# Power.net
KiCad netlist of a schematic drawn in Altium Designer
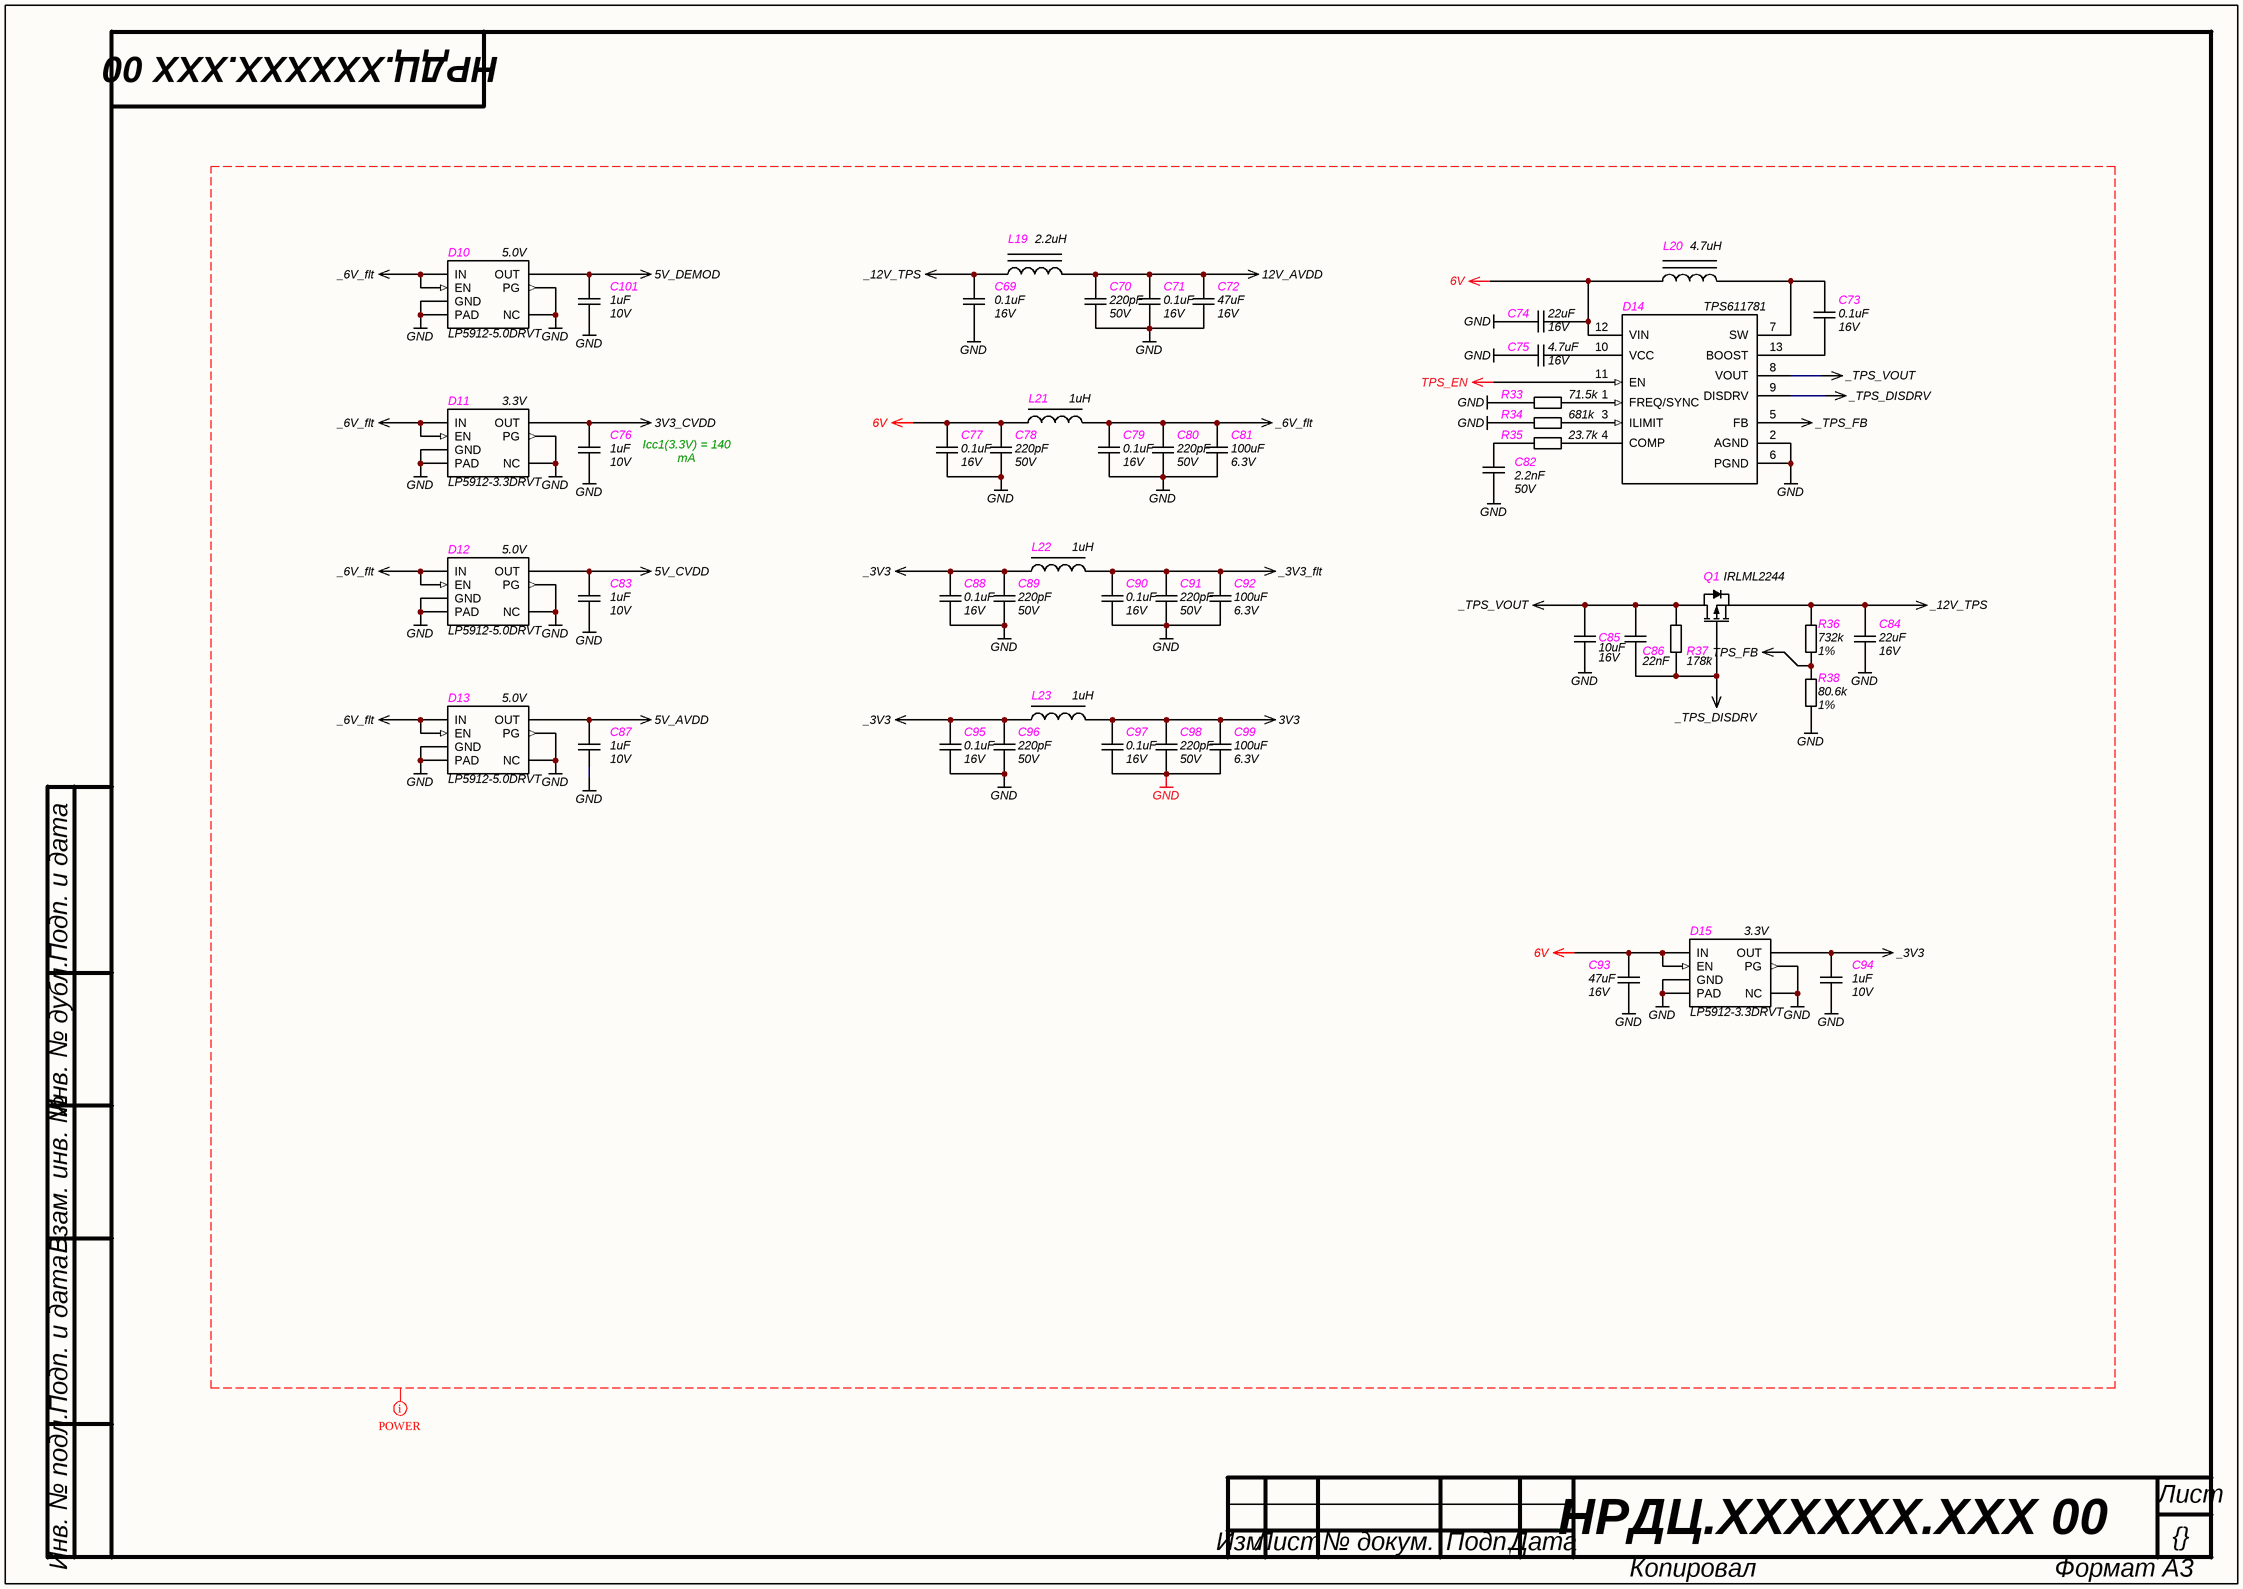
[diagram p0: Power.SchDoc]

(export (version "E")
  (design (tool "Eeschema 10.0.6"))
  (components
    (comp (ref "C69")
      (value "0.1uF")
      (footprint "C0402")
      (description "SMD Capacitor")
      (fields
        (field (name "MANUFACTURER") "Murata")
        (field (name "TOLERANCE") "10%")
        (field (name "VOLTAGE") "16V")
      )
      (libsource (lib "Kintex_SDR") (part "CAP"))
    )
    (comp (ref "C70")
      (value "220pF")
      (footprint "C0603")
      (description "SMD Capacitor")
      (fields
        (field (name "MANUFACTURER") "KEMET")
        (field (name "TOLERANCE") "10%")
        (field (name "VOLTAGE") "50V")
      )
      (libsource (lib "Kintex_SDR") (part "CAP"))
    )
    (comp (ref "C71")
      (value "0.1uF")
      (footprint "C0402")
      (description "SMD Capacitor")
      (fields
        (field (name "MANUFACTURER") "Murata")
        (field (name "TOLERANCE") "10%")
        (field (name "VOLTAGE") "16V")
      )
      (libsource (lib "Kintex_SDR") (part "CAP"))
    )
    (comp (ref "C72")
      (value "47uF")
      (footprint "C1210")
      (description "SMD Capacitor")
      (fields
        (field (name "MANUFACTURER") "Murata")
        (field (name "TOLERANCE") "10%")
        (field (name "VOLTAGE") "16V")
      )
      (libsource (lib "Kintex_SDR") (part "CAP uF"))
    )
    (comp (ref "C73")
      (value "0.1uF")
      (footprint "C0402")
      (description "SMD Capacitor")
      (fields
        (field (name "MANUFACTURER") "Murata")
        (field (name "TOLERANCE") "10%")
        (field (name "VOLTAGE") "16V")
      )
      (libsource (lib "Kintex_SDR") (part "CAP"))
    )
    (comp (ref "C74")
      (value "22uF")
      (footprint "C0805")
      (description "SMD Capacitor")
      (fields
        (field (name "MANUFACTURER") "Murata")
        (field (name "TOLERANCE") "±20%")
        (field (name "VOLTAGE") "16V")
      )
      (libsource (lib "Kintex_SDR") (part "CAP uF"))
    )
    (comp (ref "C75")
      (value "4.7uF")
      (footprint "C0603")
      (description "SMD Capacitor")
      (fields
        (field (name "MANUFACTURER") "Murata")
        (field (name "TOLERANCE") "10%")
        (field (name "VOLTAGE") "16V")
      )
      (libsource (lib "Kintex_SDR") (part "CAP"))
    )
    (comp (ref "C76")
      (value "1uF")
      (footprint "C0805")
      (description "SMD Capacitor")
      (fields
        (field (name "MANUFACTURER") "Murata")
        (field (name "TOLERANCE") "10%")
        (field (name "VOLTAGE") "10V")
      )
      (libsource (lib "Kintex_SDR") (part "CAP"))
    )
    (comp (ref "C77")
      (value "0.1uF")
      (footprint "C0402")
      (description "SMD Capacitor")
      (fields
        (field (name "MANUFACTURER") "Murata")
        (field (name "TOLERANCE") "10%")
        (field (name "VOLTAGE") "16V")
      )
      (libsource (lib "Kintex_SDR") (part "CAP"))
    )
    (comp (ref "C78")
      (value "220pF")
      (footprint "C0603")
      (description "SMD Capacitor")
      (fields
        (field (name "MANUFACTURER") "KEMET")
        (field (name "TOLERANCE") "10%")
        (field (name "VOLTAGE") "50V")
      )
      (libsource (lib "Kintex_SDR") (part "CAP"))
    )
    (comp (ref "C79")
      (value "0.1uF")
      (footprint "C0402")
      (description "SMD Capacitor")
      (fields
        (field (name "MANUFACTURER") "Murata")
        (field (name "TOLERANCE") "10%")
        (field (name "VOLTAGE") "16V")
      )
      (libsource (lib "Kintex_SDR") (part "CAP"))
    )
    (comp (ref "C80")
      (value "220pF")
      (footprint "C0603")
      (description "SMD Capacitor")
      (fields
        (field (name "MANUFACTURER") "KEMET")
        (field (name "TOLERANCE") "10%")
        (field (name "VOLTAGE") "50V")
      )
      (libsource (lib "Kintex_SDR") (part "CAP"))
    )
    (comp (ref "C81")
      (value "100uF")
      (footprint "C1210")
      (description "SMD Capacitor")
      (fields
        (field (name "MANUFACTURER") "Murata")
        (field (name "TOLERANCE") "20%")
        (field (name "VOLTAGE") "6.3V")
      )
      (libsource (lib "Kintex_SDR") (part "CAP uF"))
    )
    (comp (ref "C82")
      (value "2.2nF")
      (footprint "C0603")
      (description "SMD Capacitor")
      (fields
        (field (name "MANUFACTURER") "Murata")
        (field (name "TOLERANCE") "±5%")
        (field (name "VOLTAGE") "50V")
      )
      (libsource (lib "Kintex_SDR") (part "CAP"))
    )
    (comp (ref "C83")
      (value "1uF")
      (footprint "C0805")
      (description "SMD Capacitor")
      (fields
        (field (name "MANUFACTURER") "Murata")
        (field (name "TOLERANCE") "10%")
        (field (name "VOLTAGE") "10V")
      )
      (libsource (lib "Kintex_SDR") (part "CAP"))
    )
    (comp (ref "C84")
      (value "22uF")
      (footprint "C0805")
      (description "SMD Capacitor")
      (fields
        (field (name "MANUFACTURER") "Murata")
        (field (name "TOLERANCE") "±20%")
        (field (name "VOLTAGE") "16V")
      )
      (libsource (lib "Kintex_SDR") (part "CAP uF"))
    )
    (comp (ref "C85")
      (value "10uF")
      (footprint "C0805")
      (description "SMD Capacitor")
      (fields
        (field (name "MANUFACTURER") "Murata")
        (field (name "TOLERANCE") "±10%")
        (field (name "VOLTAGE") "16V")
      )
      (libsource (lib "Kintex_SDR") (part "CAP uF"))
    )
    (comp (ref "C86")
      (value "22nF")
      (footprint "C0402")
      (description "SMD Capacitor")
      (fields (field (name "MANUFACTURER") "Murata") (field (name "TOLERANCE") "10%"))
      (libsource (lib "Kintex_SDR") (part "CAP"))
    )
    (comp (ref "C87")
      (value "1uF")
      (footprint "C0805")
      (description "SMD Capacitor")
      (fields
        (field (name "MANUFACTURER") "Murata")
        (field (name "TOLERANCE") "10%")
        (field (name "VOLTAGE") "10V")
      )
      (libsource (lib "Kintex_SDR") (part "CAP"))
    )
    (comp (ref "C88")
      (value "0.1uF")
      (footprint "C0402")
      (description "SMD Capacitor")
      (fields
        (field (name "MANUFACTURER") "Murata")
        (field (name "TOLERANCE") "10%")
        (field (name "VOLTAGE") "16V")
      )
      (libsource (lib "Kintex_SDR") (part "CAP"))
    )
    (comp (ref "C89")
      (value "220pF")
      (footprint "C0603")
      (description "SMD Capacitor")
      (fields
        (field (name "MANUFACTURER") "KEMET")
        (field (name "TOLERANCE") "10%")
        (field (name "VOLTAGE") "50V")
      )
      (libsource (lib "Kintex_SDR") (part "CAP"))
    )
    (comp (ref "C90")
      (value "0.1uF")
      (footprint "C0402")
      (description "SMD Capacitor")
      (fields
        (field (name "MANUFACTURER") "Murata")
        (field (name "TOLERANCE") "10%")
        (field (name "VOLTAGE") "16V")
      )
      (libsource (lib "Kintex_SDR") (part "CAP"))
    )
    (comp (ref "C91")
      (value "220pF")
      (footprint "C0603")
      (description "SMD Capacitor")
      (fields
        (field (name "MANUFACTURER") "KEMET")
        (field (name "TOLERANCE") "10%")
        (field (name "VOLTAGE") "50V")
      )
      (libsource (lib "Kintex_SDR") (part "CAP"))
    )
    (comp (ref "C92")
      (value "100uF")
      (footprint "C1210")
      (description "SMD Capacitor")
      (fields
        (field (name "MANUFACTURER") "Murata")
        (field (name "TOLERANCE") "20%")
        (field (name "VOLTAGE") "6.3V")
      )
      (libsource (lib "Kintex_SDR") (part "CAP uF"))
    )
    (comp (ref "C93")
      (value "47uF")
      (footprint "C1210")
      (description "SMD Capacitor")
      (fields
        (field (name "MANUFACTURER") "Murata")
        (field (name "TOLERANCE") "10%")
        (field (name "VOLTAGE") "16V")
      )
      (libsource (lib "Kintex_SDR") (part "CAP uF"))
    )
    (comp (ref "C94")
      (value "1uF")
      (footprint "C0805")
      (description "SMD Capacitor")
      (fields
        (field (name "MANUFACTURER") "Murata")
        (field (name "TOLERANCE") "10%")
        (field (name "VOLTAGE") "10V")
      )
      (libsource (lib "Kintex_SDR") (part "CAP"))
    )
    (comp (ref "C95")
      (value "0.1uF")
      (footprint "C0402")
      (description "SMD Capacitor")
      (fields
        (field (name "MANUFACTURER") "Murata")
        (field (name "TOLERANCE") "10%")
        (field (name "VOLTAGE") "16V")
      )
      (libsource (lib "Kintex_SDR") (part "CAP"))
    )
    (comp (ref "C96")
      (value "220pF")
      (footprint "C0603")
      (description "SMD Capacitor")
      (fields
        (field (name "MANUFACTURER") "KEMET")
        (field (name "TOLERANCE") "10%")
        (field (name "VOLTAGE") "50V")
      )
      (libsource (lib "Kintex_SDR") (part "CAP"))
    )
    (comp (ref "C97")
      (value "0.1uF")
      (footprint "C0402")
      (description "SMD Capacitor")
      (fields
        (field (name "MANUFACTURER") "Murata")
        (field (name "TOLERANCE") "10%")
        (field (name "VOLTAGE") "16V")
      )
      (libsource (lib "Kintex_SDR") (part "CAP"))
    )
    (comp (ref "C98")
      (value "220pF")
      (footprint "C0603")
      (description "SMD Capacitor")
      (fields
        (field (name "MANUFACTURER") "KEMET")
        (field (name "TOLERANCE") "10%")
        (field (name "VOLTAGE") "50V")
      )
      (libsource (lib "Kintex_SDR") (part "CAP"))
    )
    (comp (ref "C99")
      (value "100uF")
      (footprint "C1210")
      (description "SMD Capacitor")
      (fields
        (field (name "MANUFACTURER") "Murata")
        (field (name "TOLERANCE") "20%")
        (field (name "VOLTAGE") "6.3V")
      )
      (libsource (lib "Kintex_SDR") (part "CAP uF"))
    )
    (comp (ref "C101")
      (value "1uF")
      (footprint "C0805")
      (description "SMD Capacitor")
      (fields
        (field (name "MANUFACTURER") "Murata")
        (field (name "TOLERANCE") "10%")
        (field (name "VOLTAGE") "10V")
      )
      (libsource (lib "Kintex_SDR") (part "CAP"))
    )
    (comp (ref "D10")
      (value "LP5912")
      (footprint "DBLib:WSON-6")
      (description "LP5912 500-mA Low-Noise, Low-IQ LDO")
      (fields
        (field (name "MANUFACTURER") "Texas Instruments")
        (field (name "NAME") "LP5912-5.0DRVT")
        (field (name "VOLTAGE") "5.0V")
      )
      (libsource (lib "DBLib") (part "LP5912"))
    )
    (comp (ref "D11")
      (value "LP5912")
      (footprint "DBLib:WSON-6")
      (description "LP5912 500-mA Low-Noise, Low-IQ LDO")
      (fields
        (field (name "MANUFACTURER") "Texas Instruments")
        (field (name "NAME") "LP5912-3.3DRVT")
        (field (name "VOLTAGE") "3.3V")
      )
      (libsource (lib "DBLib") (part "LP5912"))
    )
    (comp (ref "D12")
      (value "LP5912")
      (footprint "DBLib:WSON-6")
      (description "LP5912 500-mA Low-Noise, Low-IQ LDO")
      (fields
        (field (name "MANUFACTURER") "Texas Instruments")
        (field (name "NAME") "LP5912-5.0DRVT")
        (field (name "VOLTAGE") "5.0V")
      )
      (libsource (lib "DBLib") (part "LP5912"))
    )
    (comp (ref "D13")
      (value "LP5912")
      (footprint "DBLib:WSON-6")
      (description "LP5912 500-mA Low-Noise, Low-IQ LDO")
      (fields
        (field (name "MANUFACTURER") "Texas Instruments")
        (field (name "NAME") "LP5912-5.0DRVT")
        (field (name "VOLTAGE") "5.0V")
      )
      (libsource (lib "DBLib") (part "LP5912"))
    )
    (comp (ref "D14")
      (value "TPS611781")
      (footprint "DBLib:TPS611781x")
      (description "10-A Fully-Integrated Synchronous Boost with Load Disconnect Control")
      (fields (field (name "MANUFACTURER") "Texas Instruments") (field (name "VOLTAGE") "4.5 V to 20 V"))
      (libsource (lib "DBLib") (part "TPS611781"))
    )
    (comp (ref "D15")
      (value "LP5912")
      (footprint "DBLib:WSON-6")
      (description "LP5912 500-mA Low-Noise, Low-IQ LDO")
      (fields
        (field (name "MANUFACTURER") "Texas Instruments")
        (field (name "NAME") "LP5912-3.3DRVT")
        (field (name "VOLTAGE") "3.3V")
      )
      (libsource (lib "DBLib") (part "LP5912"))
    )
    (comp (ref "L19")
      (value "2.2uH")
      (footprint "XAL4020")
      (description "Magnetic-Core Inductor")
      (fields (field (name "MANUFACTURER") "Coilcraft") (field (name "TOLERANCE") "±30%"))
      (libsource (lib "Kintex_SDR") (part "Inductor PWR"))
    )
    (comp (ref "L20")
      (value "4.7uH")
      (footprint "XAL4030")
      (description "Magnetic-Core Inductor")
      (fields (field (name "MANUFACTURER") "Coilcraft") (field (name "TOLERANCE") "±30%"))
      (libsource (lib "Kintex_SDR") (part "Inductor PWR"))
    )
    (comp (ref "L21")
      (value "1uH")
      (footprint "L1210_Murata LQH")
      (description "Inductor Power Lines")
      (fields (field (name "MANUFACTURER") "Murata") (field (name "TOLERANCE") "5%"))
      (libsource (lib "Kintex_SDR") (part "Inductor LF"))
    )
    (comp (ref "L22")
      (value "1uH")
      (footprint "L1210_Murata LQH")
      (description "Inductor Power Lines")
      (fields (field (name "MANUFACTURER") "Murata") (field (name "TOLERANCE") "5%"))
      (libsource (lib "Kintex_SDR") (part "Inductor LF"))
    )
    (comp (ref "L23")
      (value "1uH")
      (footprint "L1210_Murata LQH")
      (description "Inductor Power Lines")
      (fields (field (name "MANUFACTURER") "Murata") (field (name "TOLERANCE") "5%"))
      (libsource (lib "Kintex_SDR") (part "Inductor LF"))
    )
    (comp (ref "Q1")
      (value "IRLML2244")
      (footprint "DBLib:SOT-23")
      (description "P-Channel MOSFET")
      (fields (field (name "VOLTAGE") "-20V"))
      (libsource (lib "DBLib") (part "IRLML2244"))
    )
    (comp (ref "R33")
      (value "71.5k")
      (footprint "R0402")
      (description "SMD Resistor")
      (fields (field (name "POWER") "0.063 Wt") (field (name "TOLERANCE") "1%"))
      (libsource (lib "Kintex_SDR") (part "RES"))
    )
    (comp (ref "R34")
      (value "681k")
      (footprint "R0402")
      (description "SMD Resistor")
      (fields (field (name "POWER") "0.063 Wt") (field (name "TOLERANCE") "1%"))
      (libsource (lib "Kintex_SDR") (part "RES"))
    )
    (comp (ref "R35")
      (value "23.7k")
      (footprint "R0603")
      (description "SMD Resistor")
      (fields (field (name "POWER") "0.1 Wt") (field (name "TOLERANCE") "1%"))
      (libsource (lib "Kintex_SDR") (part "RES"))
    )
    (comp (ref "R36")
      (value "732k")
      (footprint "R0402")
      (description "SMD Resistor")
      (fields
        (field (name "POWER") "0.063 Wt")
        (field (name "TOLERANCE") "1%")
        (field (name "MANUFACTURER") "Panasonic Electronic Components")
      )
      (libsource (lib "") (part "RES_1"))
    )
    (comp (ref "R37")
      (value "178k")
      (footprint "R0402")
      (description "SMD Resistor")
      (fields (field (name "POWER") "0.063 Wt") (field (name "TOLERANCE") "1%"))
      (libsource (lib "") (part "RES_1"))
    )
    (comp (ref "R38")
      (value "80.6k")
      (footprint "R0402")
      (description "SMD Resistor")
      (fields
        (field (name "POWER") "0.063 Wt")
        (field (name "TOLERANCE") "1%")
        (field (name "MANUFACTURER") "Panasonic Electronic Components")
      )
      (libsource (lib "") (part "RES_1"))
    )
  )
  (nets
    (net (code "1") (name "3V3") (class "Default")
      (node (ref "C97") (pin "2") (pinfunction "2_2") (pintype "passive"))
      (node (ref "C98") (pin "2") (pinfunction "2_2") (pintype "passive"))
      (node (ref "C99") (pin "2") (pinfunction "2_2") (pintype "passive"))
      (node (ref "L23") (pin "2") (pinfunction "2_2") (pintype "passive"))
    )
    (net (code "2") (name "3V3_CVDD") (class "Default")
      (node (ref "C76") (pin "1") (pinfunction "1_1") (pintype "passive"))
      (node (ref "D11") (pin "1") (pinfunction "OUT_1") (pintype "passive"))
    )
    (net (code "3") (name "5V_AVDD") (class "Default")
      (node (ref "C87") (pin "1") (pinfunction "1_1") (pintype "passive"))
      (node (ref "D13") (pin "1") (pinfunction "OUT_1") (pintype "passive"))
    )
    (net (code "4") (name "5V_CVDD") (class "Default")
      (node (ref "C83") (pin "1") (pinfunction "1_1") (pintype "passive"))
      (node (ref "D12") (pin "1") (pinfunction "OUT_1") (pintype "passive"))
    )
    (net (code "5") (name "5V_DEMOD") (class "Default")
      (node (ref "C101") (pin "1") (pinfunction "1_1") (pintype "passive"))
      (node (ref "D10") (pin "1") (pinfunction "OUT_1") (pintype "passive"))
    )
    (net (code "6") (name "6V") (class "Default")
      (node (ref "C74") (pin "1") (pinfunction "1_1") (pintype "passive"))
      (node (ref "C77") (pin "2") (pinfunction "2_2") (pintype "passive"))
      (node (ref "C78") (pin "2") (pinfunction "2_2") (pintype "passive"))
      (node (ref "C93") (pin "2") (pinfunction "2_2") (pintype "passive"))
      (node (ref "D14") (pin "12") (pinfunction "VIN_12") (pintype "passive"))
      (node (ref "D15") (pin "4") (pinfunction "EN_4") (pintype "input"))
      (node (ref "D15") (pin "6") (pinfunction "IN_6") (pintype "passive"))
      (node (ref "L20") (pin "1") (pinfunction "1_1") (pintype "passive"))
      (node (ref "L21") (pin "1") (pinfunction "1_1") (pintype "passive"))
    )
    (net (code "7") (name "12V_AVDD") (class "Default")
      (node (ref "C70") (pin "2") (pinfunction "2_2") (pintype "passive"))
      (node (ref "C71") (pin "2") (pinfunction "2_2") (pintype "passive"))
      (node (ref "C72") (pin "2") (pinfunction "2_2") (pintype "passive"))
      (node (ref "L19") (pin "2") (pinfunction "2_2") (pintype "passive"))
    )
    (net (code "8") (name "GND") (class "Default")
      (node (ref "C101") (pin "2") (pinfunction "2_2") (pintype "passive"))
      (node (ref "C69") (pin "1") (pinfunction "1_1") (pintype "passive"))
      (node (ref "C70") (pin "1") (pinfunction "1_1") (pintype "passive"))
      (node (ref "C71") (pin "1") (pinfunction "1_1") (pintype "passive"))
      (node (ref "C72") (pin "1") (pinfunction "1_1") (pintype "passive"))
      (node (ref "C74") (pin "2") (pinfunction "2_2") (pintype "passive"))
      (node (ref "C75") (pin "2") (pinfunction "2_2") (pintype "passive"))
      (node (ref "C76") (pin "2") (pinfunction "2_2") (pintype "passive"))
      (node (ref "C77") (pin "1") (pinfunction "1_1") (pintype "passive"))
      (node (ref "C78") (pin "1") (pinfunction "1_1") (pintype "passive"))
      (node (ref "C79") (pin "1") (pinfunction "1_1") (pintype "passive"))
      (node (ref "C80") (pin "1") (pinfunction "1_1") (pintype "passive"))
      (node (ref "C81") (pin "1") (pinfunction "1_1") (pintype "passive"))
      (node (ref "C82") (pin "1") (pinfunction "1_1") (pintype "passive"))
      (node (ref "C83") (pin "2") (pinfunction "2_2") (pintype "passive"))
      (node (ref "C84") (pin "1") (pinfunction "1_1") (pintype "passive"))
      (node (ref "C85") (pin "1") (pinfunction "1_1") (pintype "passive"))
      (node (ref "C87") (pin "2") (pinfunction "2_2") (pintype "passive"))
      (node (ref "C88") (pin "1") (pinfunction "1_1") (pintype "passive"))
      (node (ref "C89") (pin "1") (pinfunction "1_1") (pintype "passive"))
      (node (ref "C90") (pin "1") (pinfunction "1_1") (pintype "passive"))
      (node (ref "C91") (pin "1") (pinfunction "1_1") (pintype "passive"))
      (node (ref "C92") (pin "1") (pinfunction "1_1") (pintype "passive"))
      (node (ref "C93") (pin "1") (pinfunction "1_1") (pintype "passive"))
      (node (ref "C94") (pin "2") (pinfunction "2_2") (pintype "passive"))
      (node (ref "C95") (pin "1") (pinfunction "1_1") (pintype "passive"))
      (node (ref "C96") (pin "1") (pinfunction "1_1") (pintype "passive"))
      (node (ref "C97") (pin "1") (pinfunction "1_1") (pintype "passive"))
      (node (ref "C98") (pin "1") (pinfunction "1_1") (pintype "passive"))
      (node (ref "C99") (pin "1") (pinfunction "1_1") (pintype "passive"))
      (node (ref "D10") (pin "0") (pinfunction "PAD_0") (pintype "passive"))
      (node (ref "D10") (pin "2") (pinfunction "NC_2") (pintype "passive"))
      (node (ref "D10") (pin "3") (pinfunction "PG_3") (pintype "output"))
      (node (ref "D10") (pin "5") (pinfunction "GND_5") (pintype "passive"))
      (node (ref "D11") (pin "0") (pinfunction "PAD_0") (pintype "passive"))
      (node (ref "D11") (pin "2") (pinfunction "NC_2") (pintype "passive"))
      (node (ref "D11") (pin "3") (pinfunction "PG_3") (pintype "output"))
      (node (ref "D11") (pin "5") (pinfunction "GND_5") (pintype "passive"))
      (node (ref "D12") (pin "0") (pinfunction "PAD_0") (pintype "passive"))
      (node (ref "D12") (pin "2") (pinfunction "NC_2") (pintype "passive"))
      (node (ref "D12") (pin "3") (pinfunction "PG_3") (pintype "output"))
      (node (ref "D12") (pin "5") (pinfunction "GND_5") (pintype "passive"))
      (node (ref "D13") (pin "0") (pinfunction "PAD_0") (pintype "passive"))
      (node (ref "D13") (pin "2") (pinfunction "NC_2") (pintype "passive"))
      (node (ref "D13") (pin "3") (pinfunction "PG_3") (pintype "output"))
      (node (ref "D13") (pin "5") (pinfunction "GND_5") (pintype "passive"))
      (node (ref "D14") (pin "2") (pinfunction "AGND_2") (pintype "passive"))
      (node (ref "D14") (pin "6") (pinfunction "PGND_6") (pintype "passive"))
      (node (ref "D15") (pin "0") (pinfunction "PAD_0") (pintype "passive"))
      (node (ref "D15") (pin "2") (pinfunction "NC_2") (pintype "passive"))
      (node (ref "D15") (pin "3") (pinfunction "PG_3") (pintype "output"))
      (node (ref "D15") (pin "5") (pinfunction "GND_5") (pintype "passive"))
      (node (ref "R33") (pin "1") (pinfunction "1_1") (pintype "passive"))
      (node (ref "R34") (pin "1") (pinfunction "1_1") (pintype "passive"))
      (node (ref "R38") (pin "1") (pinfunction "1_1") (pintype "passive"))
    )
    (net (code "9") (name "Net-(C82-Pad2)") (class "Default")
      (node (ref "C82") (pin "2") (pinfunction "2_2") (pintype "passive"))
      (node (ref "R35") (pin "1") (pinfunction "1_1") (pintype "passive"))
    )
    (net (code "10") (name "Net-(D14-BOOST)") (class "Default")
      (node (ref "C73") (pin "1") (pinfunction "1_1") (pintype "passive"))
      (node (ref "D14") (pin "13") (pinfunction "BOOST_13") (pintype "passive"))
    )
    (net (code "11") (name "Net-(D14-COMP)") (class "Default")
      (node (ref "D14") (pin "4") (pinfunction "COMP_4") (pintype "passive"))
      (node (ref "R35") (pin "2") (pinfunction "2_2") (pintype "passive"))
    )
    (net (code "12") (name "Net-(D14-FREQ{slash}SYNC)") (class "Default")
      (node (ref "D14") (pin "1") (pinfunction "FREQ/SYNC_1") (pintype "input"))
      (node (ref "R33") (pin "2") (pinfunction "2_2") (pintype "passive"))
    )
    (net (code "13") (name "Net-(D14-ILIMIT)") (class "Default")
      (node (ref "D14") (pin "3") (pinfunction "ILIMIT_3") (pintype "input"))
      (node (ref "R34") (pin "2") (pinfunction "2_2") (pintype "passive"))
    )
    (net (code "14") (name "Net-(D14-SW)") (class "Default")
      (node (ref "C73") (pin "2") (pinfunction "2_2") (pintype "passive"))
      (node (ref "D14") (pin "7") (pinfunction "SW_7") (pintype "passive"))
      (node (ref "L20") (pin "2") (pinfunction "2_2") (pintype "passive"))
    )
    (net (code "15") (name "Net-(D14-VCC)") (class "Default")
      (node (ref "C75") (pin "1") (pinfunction "1_1") (pintype "passive"))
      (node (ref "D14") (pin "10") (pinfunction "VCC_10") (pintype "passive"))
    )
    (net (code "16") (name "TPS_EN") (class "Default")
      (node (ref "D14") (pin "11") (pinfunction "EN_11") (pintype "input"))
    )
    (net (code "17") (name "_3V3") (class "Default")
      (node (ref "C88") (pin "2") (pinfunction "2_2") (pintype "passive"))
      (node (ref "C89") (pin "2") (pinfunction "2_2") (pintype "passive"))
      (node (ref "C94") (pin "1") (pinfunction "1_1") (pintype "passive"))
      (node (ref "C95") (pin "2") (pinfunction "2_2") (pintype "passive"))
      (node (ref "C96") (pin "2") (pinfunction "2_2") (pintype "passive"))
      (node (ref "D15") (pin "1") (pinfunction "OUT_1") (pintype "passive"))
      (node (ref "L22") (pin "1") (pinfunction "1_1") (pintype "passive"))
      (node (ref "L23") (pin "1") (pinfunction "1_1") (pintype "passive"))
    )
    (net (code "18") (name "_3V3_flt") (class "Default")
      (node (ref "C90") (pin "2") (pinfunction "2_2") (pintype "passive"))
      (node (ref "C91") (pin "2") (pinfunction "2_2") (pintype "passive"))
      (node (ref "C92") (pin "2") (pinfunction "2_2") (pintype "passive"))
      (node (ref "L22") (pin "2") (pinfunction "2_2") (pintype "passive"))
    )
    (net (code "19") (name "_6V_flt") (class "Default")
      (node (ref "C79") (pin "2") (pinfunction "2_2") (pintype "passive"))
      (node (ref "C80") (pin "2") (pinfunction "2_2") (pintype "passive"))
      (node (ref "C81") (pin "2") (pinfunction "2_2") (pintype "passive"))
      (node (ref "D10") (pin "4") (pinfunction "EN_4") (pintype "input"))
      (node (ref "D10") (pin "6") (pinfunction "IN_6") (pintype "passive"))
      (node (ref "D11") (pin "4") (pinfunction "EN_4") (pintype "input"))
      (node (ref "D11") (pin "6") (pinfunction "IN_6") (pintype "passive"))
      (node (ref "D12") (pin "4") (pinfunction "EN_4") (pintype "input"))
      (node (ref "D12") (pin "6") (pinfunction "IN_6") (pintype "passive"))
      (node (ref "D13") (pin "4") (pinfunction "EN_4") (pintype "input"))
      (node (ref "D13") (pin "6") (pinfunction "IN_6") (pintype "passive"))
      (node (ref "L21") (pin "2") (pinfunction "2_2") (pintype "passive"))
    )
    (net (code "20") (name "_12V_TPS") (class "Default")
      (node (ref "C69") (pin "2") (pinfunction "2_2") (pintype "passive"))
      (node (ref "C84") (pin "2") (pinfunction "2_2") (pintype "passive"))
      (node (ref "L19") (pin "1") (pinfunction "1_1") (pintype "passive"))
      (node (ref "Q1") (pin "2") (pinfunction "S_2") (pintype "passive"))
      (node (ref "R36") (pin "2") (pinfunction "2_2") (pintype "passive"))
    )
    (net (code "21") (name "_TPS_DISDRV") (class "Default")
      (node (ref "C86") (pin "2") (pinfunction "2_2") (pintype "passive"))
      (node (ref "D14") (pin "9") (pinfunction "DISDRV_9") (pintype "passive"))
      (node (ref "Q1") (pin "1") (pinfunction "G_1") (pintype "passive"))
      (node (ref "R37") (pin "1") (pinfunction "1_1") (pintype "passive"))
    )
    (net (code "22") (name "_TPS_FB") (class "Default")
      (node (ref "D14") (pin "5") (pinfunction "FB_5") (pintype "passive"))
      (node (ref "R36") (pin "1") (pinfunction "1_1") (pintype "passive"))
      (node (ref "R38") (pin "2") (pinfunction "2_2") (pintype "passive"))
    )
    (net (code "23") (name "_TPS_VOUT") (class "Default")
      (node (ref "C85") (pin "2") (pinfunction "2_2") (pintype "passive"))
      (node (ref "C86") (pin "1") (pinfunction "1_1") (pintype "passive"))
      (node (ref "D14") (pin "8") (pinfunction "VOUT_8") (pintype "passive"))
      (node (ref "Q1") (pin "3") (pinfunction "D_3") (pintype "passive"))
      (node (ref "R37") (pin "2") (pinfunction "2_2") (pintype "passive"))
    )
  )
)
